# entireboard_v1.net
KiCad netlist of a schematic drawn in EAGLE
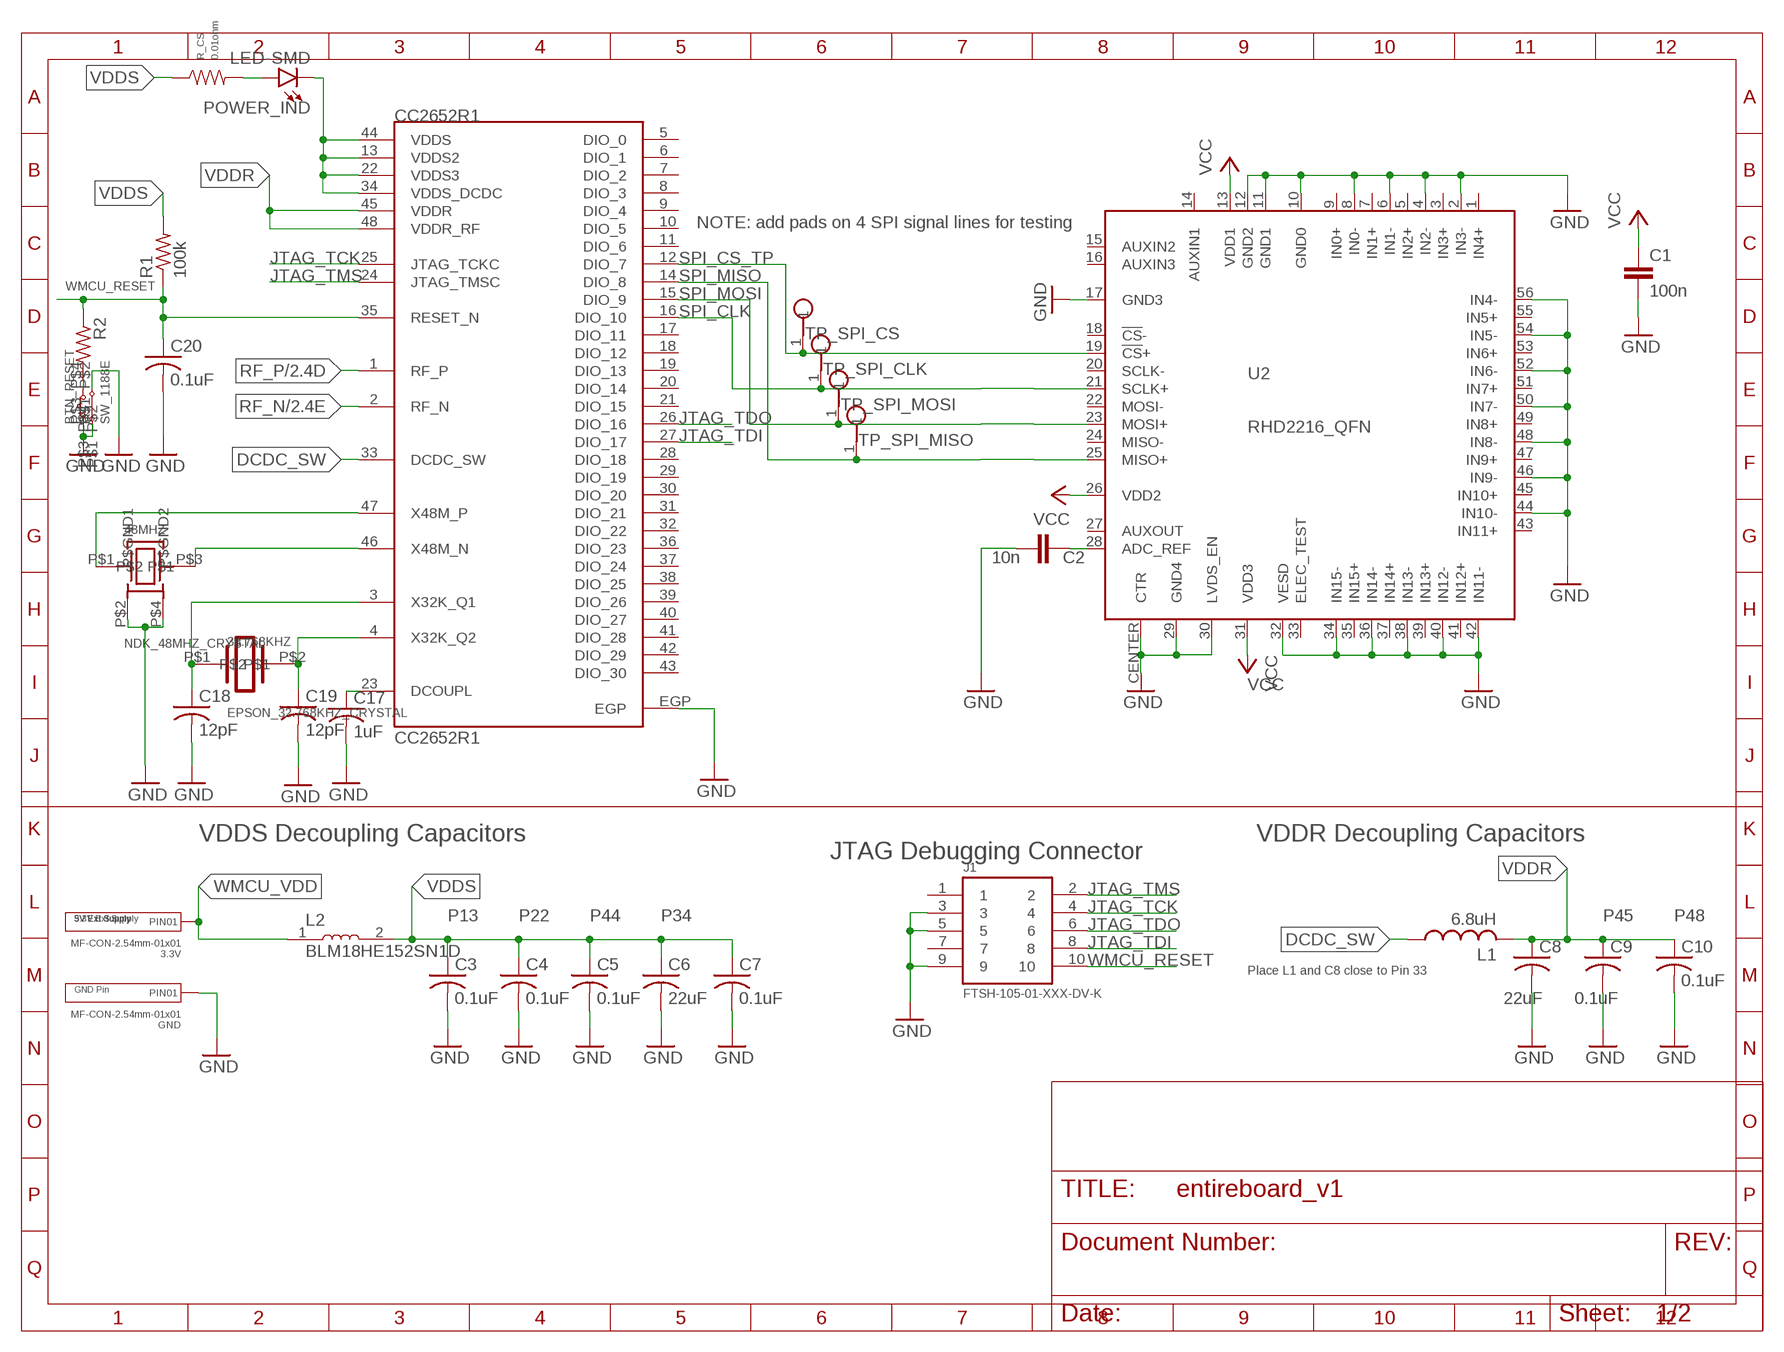
[diagram p0: schematic, sheet 1]
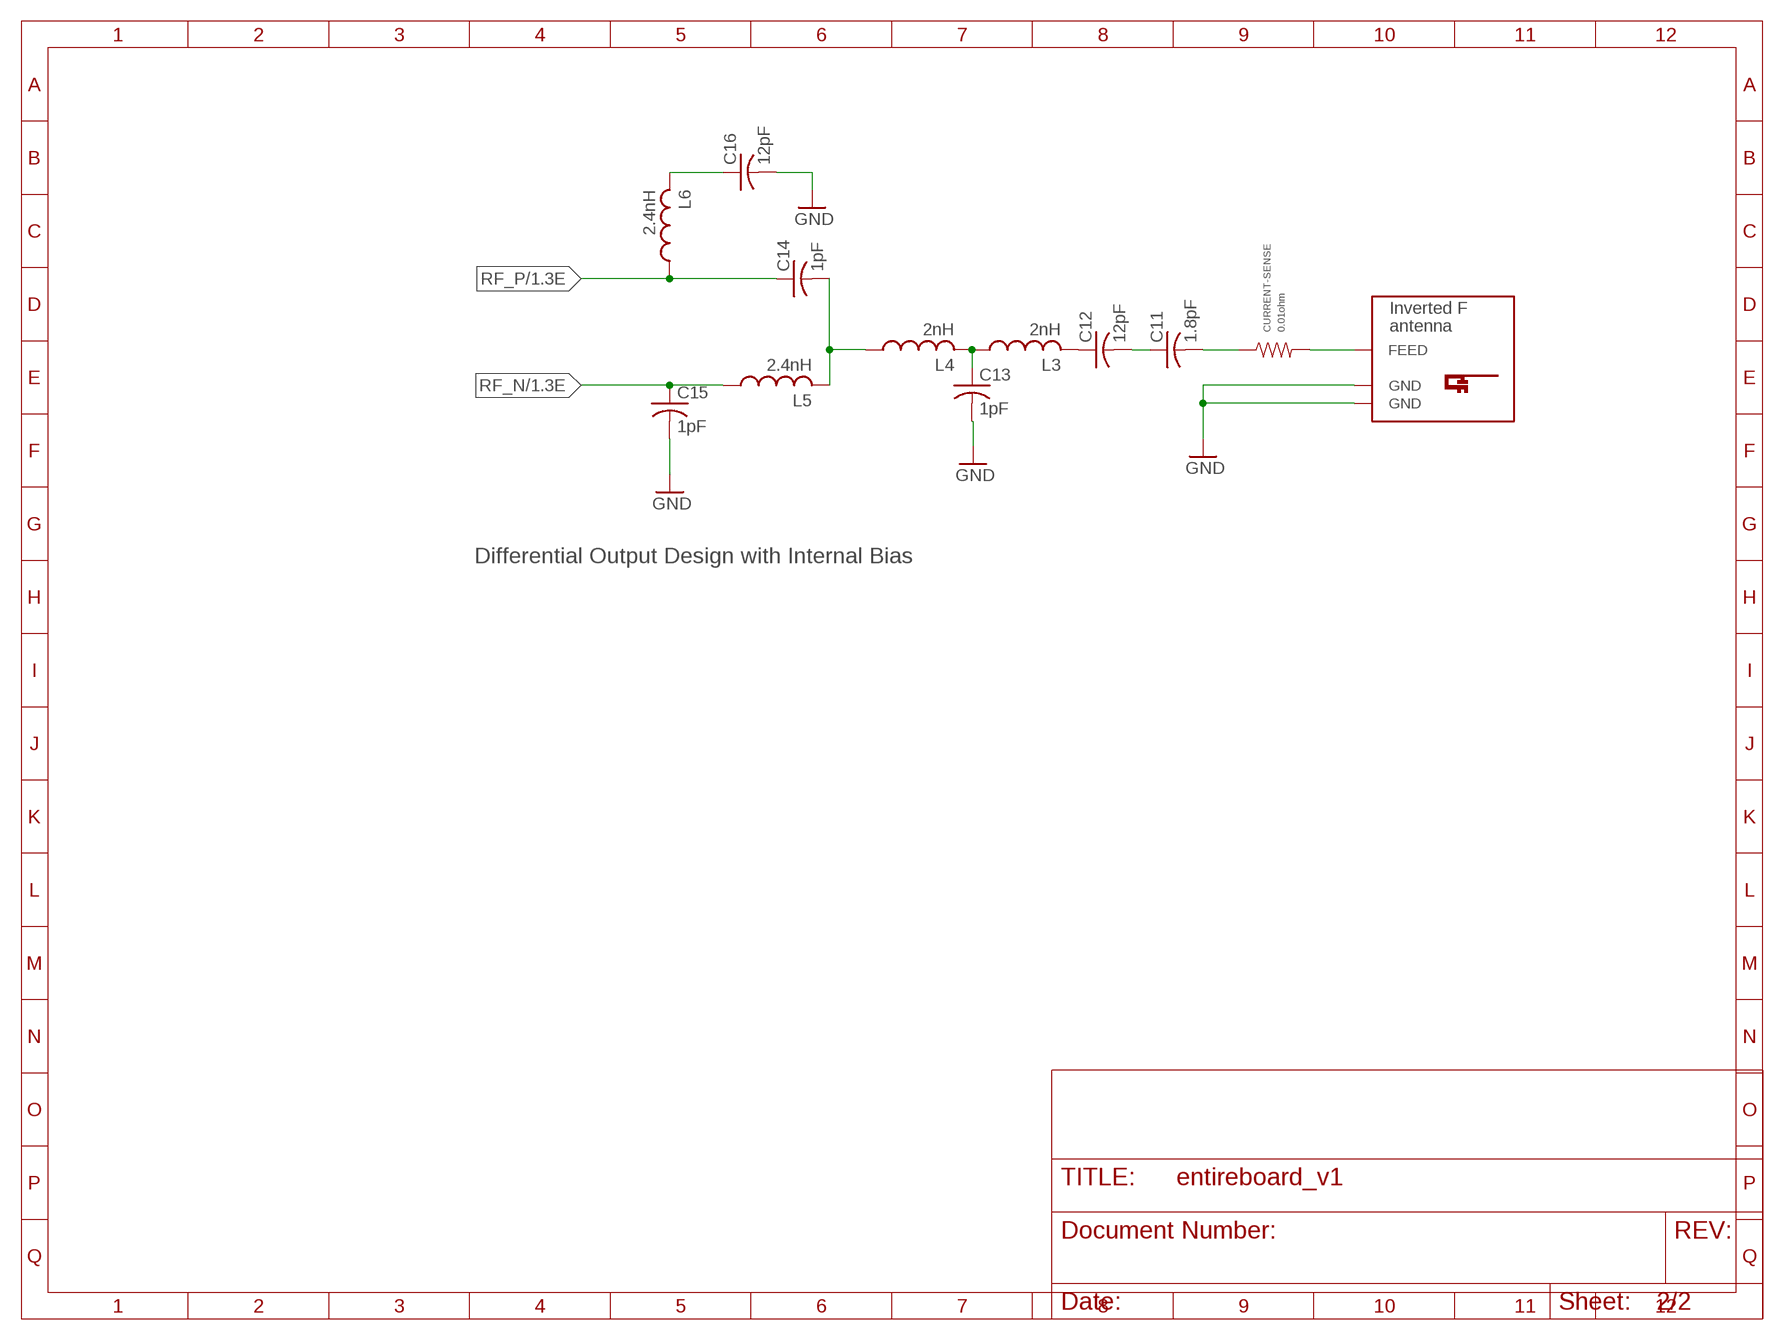
[diagram p1: schematic, sheet 2]

(export (version "E")
  (design (tool "Eeschema 10.0.6"))
  (components
    (comp (ref "3.3V")
      (value "MF-CON-2.54mm-01x01")
      (footprint "eagle-import:PTH_2.54MM_01X01")
      (fields (field (name "HOUSEPART") "YES"))
      (libsource (lib "eagle-import") (part "CON_01X01_PTH_2.54MM"))
    )
    (comp (ref "38.768KHZ")
      (value "EPSON_32.768KHZ_CRYSTAL")
      (footprint "eagle-import:2-SMD")
      (libsource (lib "eagle-import") (part "EPSON_32.768KHZ_CRYSTAL"))
    )
    (comp (ref "48MHZ")
      (value "NDK_48MHZ_CRYSTAL")
      (footprint "eagle-import:4-SMD")
      (libsource (lib "eagle-import") (part "NDK_48MHZ_CRYSTAL"))
    )
    (comp (ref "BTN_RESET")
      (value "SW_1188E")
      (footprint "eagle-import:SW_1188E")
      (libsource (lib "eagle-import") (part "SW_1188E"))
    )
    (comp (ref "C1")
      (value "100n")
      (footprint "eagle-import:0402")
      (libsource (lib "eagle-import") (part "C_0402"))
    )
    (comp (ref "C2")
      (value "10n")
      (footprint "eagle-import:0402")
      (libsource (lib "eagle-import") (part "C_0402"))
    )
    (comp (ref "C3")
      (value "0.1uF")
      (footprint "eagle-import:C0402")
      (libsource (lib "eagle-import") (part "C-USC0402"))
    )
    (comp (ref "C4")
      (value "0.1uF")
      (footprint "eagle-import:C0402")
      (libsource (lib "eagle-import") (part "C-USC0402"))
    )
    (comp (ref "C5")
      (value "0.1uF")
      (footprint "eagle-import:C0402")
      (libsource (lib "eagle-import") (part "C-USC0402"))
    )
    (comp (ref "C6")
      (value "22uF")
      (footprint "eagle-import:C0402")
      (libsource (lib "eagle-import") (part "C-USC0402"))
    )
    (comp (ref "C7")
      (value "0.1uF")
      (footprint "eagle-import:C0402")
      (libsource (lib "eagle-import") (part "C-USC0402"))
    )
    (comp (ref "C8")
      (value "22uF")
      (footprint "eagle-import:C0402")
      (libsource (lib "eagle-import") (part "C-USC0402"))
    )
    (comp (ref "C9")
      (value "0.1uF")
      (footprint "eagle-import:C0402")
      (libsource (lib "eagle-import") (part "C-USC0402"))
    )
    (comp (ref "C10")
      (value "0.1uF")
      (footprint "eagle-import:C0402")
      (libsource (lib "eagle-import") (part "C-USC0402"))
    )
    (comp (ref "C17")
      (value "1uF")
      (footprint "eagle-import:C0402")
      (libsource (lib "eagle-import") (part "C-USC0402"))
    )
    (comp (ref "C18")
      (value "12pF")
      (footprint "eagle-import:C0402")
      (libsource (lib "eagle-import") (part "C-USC0402"))
    )
    (comp (ref "C19")
      (value "12pF")
      (footprint "eagle-import:C0402")
      (libsource (lib "eagle-import") (part "C-USC0402"))
    )
    (comp (ref "C20")
      (value "0.1uF")
      (footprint "eagle-import:C0402")
      (libsource (lib "eagle-import") (part "C-USC0402"))
    )
    (comp (ref "CC2652R1")
      (value "CC2652R1")
      (footprint "eagle-import:CC2652R1_QFN-48")
      (libsource (lib "eagle-import") (part "CC2652R1"))
    )
    (comp (ref "GND")
      (value "MF-CON-2.54mm-01x01")
      (footprint "eagle-import:PTH_2.54MM_01X01")
      (fields (field (name "HOUSEPART") "YES"))
      (libsource (lib "eagle-import") (part "CON_01X01_PTH_2.54MM"))
    )
    (comp (ref "J1")
      (value "FTSH-105-01-XXX-DV-K")
      (footprint "eagle-import:FTSH-105-01-XXX-DV-K")
      (libsource (lib "eagle-import") (part "FTSH-105-01-XXX-DV-K"))
    )
    (comp (ref "L1")
      (value "6.8uH")
      (footprint "eagle-import:RHD2000_EVAL_BOARD_0805")
      (libsource (lib "eagle-import") (part "L-SMD"))
    )
    (comp (ref "L2")
      (value "BLM18HE152SN1D")
      (footprint "eagle-import:INDC1608X95")
      (fields (field (name "DIGI-KEY_PART_NUMBER") "490-5216-1-ND") (field (name "MF") "Murata Electronics"))
      (libsource (lib "eagle-import") (part "BLM18HE152SN1D"))
    )
    (comp (ref "POWER_IND")
      (value "LED-SMD")
      (footprint "eagle-import:RHD2000_EVAL_BOARD_0402")
      (libsource (lib "eagle-import") (part "LED-SMD"))
    )
    (comp (ref "R1")
      (value "100k")
      (footprint "eagle-import:R0402")
      (libsource (lib "eagle-import") (part "R-US_R0402"))
    )
    (comp (ref "R2")
      (value "R-US_R0402")
      (footprint "eagle-import:R0402")
      (libsource (lib "eagle-import") (part "R-US_R0402"))
    )
    (comp (ref "R_CS")
      (value "0.01ohm")
      (footprint "eagle-import:R0402")
      (libsource (lib "eagle-import") (part "RESISTOR_0402"))
    )
    (comp (ref "TP_SPI_CLK")
      (value "RHD2000_EVAL_BOARD_TESTPOINT_SMALL")
      (footprint "eagle-import:RHD2000_EVAL_BOARD_TESTPOINT_SMALL")
      (libsource (lib "eagle-import") (part "RHD2000_EVAL_BOARD_TESTPOINT_SMALL"))
    )
    (comp (ref "TP_SPI_CS")
      (value "RHD2000_EVAL_BOARD_TESTPOINT_SMALL")
      (footprint "eagle-import:RHD2000_EVAL_BOARD_TESTPOINT_SMALL")
      (libsource (lib "eagle-import") (part "RHD2000_EVAL_BOARD_TESTPOINT_SMALL"))
    )
    (comp (ref "TP_SPI_MISO")
      (value "RHD2000_EVAL_BOARD_TESTPOINT_SMALL")
      (footprint "eagle-import:RHD2000_EVAL_BOARD_TESTPOINT_SMALL")
      (libsource (lib "eagle-import") (part "RHD2000_EVAL_BOARD_TESTPOINT_SMALL"))
    )
    (comp (ref "TP_SPI_MOSI")
      (value "RHD2000_EVAL_BOARD_TESTPOINT_SMALL")
      (footprint "eagle-import:RHD2000_EVAL_BOARD_TESTPOINT_SMALL")
      (libsource (lib "eagle-import") (part "RHD2000_EVAL_BOARD_TESTPOINT_SMALL"))
    )
    (comp (ref "U2")
      (value "RHD2216_QFN")
      (footprint "eagle-import:QFN56_8_X_8_LARGE")
      (libsource (lib "eagle-import") (part "RHD2216_QFN"))
    )
    (comp (ref "C11")
      (value "1.8pF")
      (footprint "eagle-import:C0402")
      (libsource (lib "eagle-import") (part "C-USC0402"))
    )
    (comp (ref "C12")
      (value "12pF")
      (footprint "eagle-import:C0402")
      (libsource (lib "eagle-import") (part "C-USC0402"))
    )
    (comp (ref "C13")
      (value "1pF")
      (footprint "eagle-import:C0402")
      (libsource (lib "eagle-import") (part "C-USC0402"))
    )
    (comp (ref "C14")
      (value "1pF")
      (footprint "eagle-import:C0402")
      (libsource (lib "eagle-import") (part "C-USC0402"))
    )
    (comp (ref "C15")
      (value "1pF")
      (footprint "eagle-import:C0402")
      (libsource (lib "eagle-import") (part "C-USC0402"))
    )
    (comp (ref "C16")
      (value "12pF")
      (footprint "eagle-import:C0402")
      (libsource (lib "eagle-import") (part "C-USC0402"))
    )
    (comp (ref "CURRENT-SENSE")
      (value "0.01ohm")
      (footprint "eagle-import:R0402")
      (libsource (lib "eagle-import") (part "RESISTOR_0402"))
    )
    (comp (ref "L3")
      (value "2nH")
      (footprint "eagle-import:RHD2000_EVAL_BOARD_0805")
      (libsource (lib "eagle-import") (part "L-SMD"))
    )
    (comp (ref "L4")
      (value "2nH")
      (footprint "eagle-import:RHD2000_EVAL_BOARD_0805")
      (libsource (lib "eagle-import") (part "L-SMD"))
    )
    (comp (ref "L5")
      (value "2.4nH")
      (footprint "eagle-import:RHD2000_EVAL_BOARD_0805")
      (libsource (lib "eagle-import") (part "L-SMD"))
    )
    (comp (ref "L6")
      (value "2.4nH")
      (footprint "eagle-import:RHD2000_EVAL_BOARD_0805")
      (libsource (lib "eagle-import") (part "L-SMD"))
    )
    (comp (ref "U$2")
      (value "INVERTED_F_ANTENNA+0")
      (footprint "eagle-import:DN007+0")
      (libsource (lib "eagle-import") (part "INVERTED_F_ANTENNA+0"))
    )
  )
  (nets
    (net (code "1") (name "DCDC_SW") (class "Default")
      (node (ref "CC2652R1") (pin "33") (pinfunction "DCDC_SW_33") (pintype "bidirectional"))
      (node (ref "L1") (pin "1") (pinfunction "1_1") (pintype "passive"))
    )
    (net (code "2") (name "GND") (class "Default")
      (node (ref "48MHZ") (pin "P$2") (pinfunction "P$GND1_P$2") (pintype "bidirectional"))
      (node (ref "48MHZ") (pin "P$4") (pinfunction "P$GND2_P$4") (pintype "bidirectional"))
      (node (ref "BTN_RESET") (pin "P$1") (pinfunction "P$1_P$1") (pintype "bidirectional"))
      (node (ref "BTN_RESET") (pin "P$2") (pinfunction "P$2_P$2") (pintype "bidirectional"))
      (node (ref "BTN_RESET") (pin "P$3") (pinfunction "P$3_P$3") (pintype "bidirectional"))
      (node (ref "C1") (pin "2") (pinfunction "2_2") (pintype "passive"))
      (node (ref "C10") (pin "2") (pinfunction "2_2") (pintype "passive"))
      (node (ref "C13") (pin "2") (pinfunction "2_2") (pintype "passive"))
      (node (ref "C15") (pin "2") (pinfunction "2_2") (pintype "passive"))
      (node (ref "C16") (pin "2") (pinfunction "2_2") (pintype "passive"))
      (node (ref "C17") (pin "2") (pinfunction "2_2") (pintype "passive"))
      (node (ref "C18") (pin "2") (pinfunction "2_2") (pintype "passive"))
      (node (ref "C19") (pin "2") (pinfunction "2_2") (pintype "passive"))
      (node (ref "C2") (pin "2") (pinfunction "2_2") (pintype "passive"))
      (node (ref "C20") (pin "2") (pinfunction "2_2") (pintype "passive"))
      (node (ref "C3") (pin "2") (pinfunction "2_2") (pintype "passive"))
      (node (ref "C4") (pin "2") (pinfunction "2_2") (pintype "passive"))
      (node (ref "C5") (pin "2") (pinfunction "2_2") (pintype "passive"))
      (node (ref "C6") (pin "2") (pinfunction "2_2") (pintype "passive"))
      (node (ref "C7") (pin "2") (pinfunction "2_2") (pintype "passive"))
      (node (ref "C8") (pin "2") (pinfunction "2_2") (pintype "passive"))
      (node (ref "C9") (pin "2") (pinfunction "2_2") (pintype "passive"))
      (node (ref "CC2652R1") (pin "EGP") (pinfunction "EGP_EGP") (pintype "bidirectional"))
      (node (ref "GND") (pin "P$1") (pinfunction "PIN1_P$1") (pintype "bidirectional"))
      (node (ref "J1") (pin "3") (pinfunction "3_3") (pintype "bidirectional"))
      (node (ref "J1") (pin "5") (pinfunction "5_5") (pintype "bidirectional"))
      (node (ref "J1") (pin "9") (pinfunction "9_9") (pintype "bidirectional"))
      (node (ref "U$2") (pin "GND") (pinfunction "GND_GND") (pintype "bidirectional"))
      (node (ref "U$2") (pin "GND@1") (pinfunction "GND_GND@1") (pintype "bidirectional"))
      (node (ref "U2") (pin "10") (pinfunction "GND0_10") (pintype "input"))
      (node (ref "U2") (pin "11") (pinfunction "GND1_11") (pintype "power_in"))
      (node (ref "U2") (pin "12") (pinfunction "GND2_12") (pintype "power_in"))
      (node (ref "U2") (pin "17") (pinfunction "GND3_17") (pintype "power_in"))
      (node (ref "U2") (pin "2") (pinfunction "IN3-_2") (pintype "input"))
      (node (ref "U2") (pin "29") (pinfunction "GND4_29") (pintype "power_in"))
      (node (ref "U2") (pin "30") (pinfunction "LVDS_EN_30") (pintype "input"))
      (node (ref "U2") (pin "32") (pinfunction "VESD_32") (pintype "power_in"))
      (node (ref "U2") (pin "34") (pinfunction "IN15-_34") (pintype "input"))
      (node (ref "U2") (pin "36") (pinfunction "IN14-_36") (pintype "input"))
      (node (ref "U2") (pin "38") (pinfunction "IN13-_38") (pintype "input"))
      (node (ref "U2") (pin "4") (pinfunction "IN2-_4") (pintype "input"))
      (node (ref "U2") (pin "40") (pinfunction "IN12-_40") (pintype "input"))
      (node (ref "U2") (pin "42") (pinfunction "IN11-_42") (pintype "input"))
      (node (ref "U2") (pin "44") (pinfunction "IN10-_44") (pintype "input"))
      (node (ref "U2") (pin "46") (pinfunction "IN9-_46") (pintype "input"))
      (node (ref "U2") (pin "48") (pinfunction "IN8-_48") (pintype "input"))
      (node (ref "U2") (pin "50") (pinfunction "IN7-_50") (pintype "input"))
      (node (ref "U2") (pin "52") (pinfunction "IN6-_52") (pintype "input"))
      (node (ref "U2") (pin "54") (pinfunction "IN5-_54") (pintype "input"))
      (node (ref "U2") (pin "56") (pinfunction "IN4-_56") (pintype "input"))
      (node (ref "U2") (pin "6") (pinfunction "IN1-_6") (pintype "input"))
      (node (ref "U2") (pin "8") (pinfunction "IN0-_8") (pintype "input"))
      (node (ref "U2") (pin "CENTER") (pinfunction "CTR_CENTER") (pintype "power_in"))
    )
    (net (code "3") (name "JTAG_TCK") (class "Default")
      (node (ref "CC2652R1") (pin "25") (pinfunction "JTAG_TCKC_25") (pintype "bidirectional"))
      (node (ref "J1") (pin "4") (pinfunction "4_4") (pintype "bidirectional"))
    )
    (net (code "4") (name "JTAG_TDI") (class "Default")
      (node (ref "CC2652R1") (pin "27") (pinfunction "DIO_17_27") (pintype "bidirectional"))
      (node (ref "J1") (pin "8") (pinfunction "8_8") (pintype "bidirectional"))
    )
    (net (code "5") (name "JTAG_TDO") (class "Default")
      (node (ref "CC2652R1") (pin "26") (pinfunction "DIO_16_26") (pintype "bidirectional"))
      (node (ref "J1") (pin "6") (pinfunction "6_6") (pintype "bidirectional"))
    )
    (net (code "6") (name "JTAG_TMS") (class "Default")
      (node (ref "CC2652R1") (pin "24") (pinfunction "JTAG_TMSC_24") (pintype "bidirectional"))
      (node (ref "J1") (pin "2") (pinfunction "2_2") (pintype "bidirectional"))
    )
    (net (code "7") (name "Net-(48MHZ-P$2)") (class "Default")
      (node (ref "48MHZ") (pin "P$3") (pinfunction "P$2_P$3") (pintype "bidirectional"))
      (node (ref "CC2652R1") (pin "46") (pinfunction "X48M_N_46") (pintype "bidirectional"))
    )
    (net (code "8") (name "Net-(BTN_RESET-PadP$4)") (class "Default")
      (node (ref "BTN_RESET") (pin "P$4") (pinfunction "P$4_P$4") (pintype "bidirectional"))
      (node (ref "R2") (pin "2") (pinfunction "2_2") (pintype "passive"))
    )
    (net (code "9") (name "Net-(C11-Pad1)") (class "Default")
      (node (ref "C11") (pin "1") (pinfunction "1_1") (pintype "passive"))
      (node (ref "C12") (pin "2") (pinfunction "2_2") (pintype "passive"))
    )
    (net (code "10") (name "Net-(C11-Pad2)") (class "Default")
      (node (ref "C11") (pin "2") (pinfunction "2_2") (pintype "passive"))
      (node (ref "CURRENT-SENSE") (pin "P$1") (pinfunction "P$1_P$1") (pintype "passive"))
    )
    (net (code "11") (name "Net-(C12-Pad1)") (class "Default")
      (node (ref "C12") (pin "1") (pinfunction "1_1") (pintype "passive"))
      (node (ref "L3") (pin "2") (pinfunction "2_2") (pintype "passive"))
    )
    (net (code "12") (name "Net-(C13-Pad1)") (class "Default")
      (node (ref "C13") (pin "1") (pinfunction "1_1") (pintype "passive"))
      (node (ref "L3") (pin "1") (pinfunction "1_1") (pintype "passive"))
      (node (ref "L4") (pin "2") (pinfunction "2_2") (pintype "passive"))
    )
    (net (code "13") (name "Net-(C14-Pad2)") (class "Default")
      (node (ref "C14") (pin "2") (pinfunction "2_2") (pintype "passive"))
      (node (ref "L4") (pin "1") (pinfunction "1_1") (pintype "passive"))
      (node (ref "L5") (pin "2") (pinfunction "2_2") (pintype "passive"))
    )
    (net (code "14") (name "Net-(C16-Pad1)") (class "Default")
      (node (ref "C16") (pin "1") (pinfunction "1_1") (pintype "passive"))
      (node (ref "L6") (pin "2") (pinfunction "2_2") (pintype "passive"))
    )
    (net (code "15") (name "Net-(CC2652R1-DCOUPL)") (class "Default")
      (node (ref "C17") (pin "1") (pinfunction "1_1") (pintype "passive"))
      (node (ref "CC2652R1") (pin "23") (pinfunction "DCOUPL_23") (pintype "bidirectional"))
    )
    (net (code "16") (name "Net-(CC2652R1-X32K_Q1)") (class "Default")
      (node (ref "38.768KHZ") (pin "P$1") (pinfunction "P$1_P$1") (pintype "bidirectional"))
      (node (ref "C18") (pin "1") (pinfunction "1_1") (pintype "passive"))
      (node (ref "CC2652R1") (pin "3") (pinfunction "X32K_Q1_3") (pintype "bidirectional"))
    )
    (net (code "17") (name "Net-(CC2652R1-X32K_Q2)") (class "Default")
      (node (ref "38.768KHZ") (pin "P$2") (pinfunction "P$2_P$2") (pintype "bidirectional"))
      (node (ref "C19") (pin "1") (pinfunction "1_1") (pintype "passive"))
      (node (ref "CC2652R1") (pin "4") (pinfunction "X32K_Q2_4") (pintype "bidirectional"))
    )
    (net (code "18") (name "Net-(CC2652R1-X48M_P)") (class "Default")
      (node (ref "48MHZ") (pin "P$1") (pinfunction "P$1_P$1") (pintype "bidirectional"))
      (node (ref "CC2652R1") (pin "47") (pinfunction "X48M_P_47") (pintype "bidirectional"))
    )
    (net (code "19") (name "Net-(CURRENT-SENSE-PadP$2)") (class "Default")
      (node (ref "CURRENT-SENSE") (pin "P$2") (pinfunction "P$2_P$2") (pintype "passive"))
      (node (ref "U$2") (pin "FEED") (pinfunction "FEED_FEED") (pintype "bidirectional"))
    )
    (net (code "20") (name "Net-(POWER_IND-A)") (class "Default")
      (node (ref "POWER_IND") (pin "1") (pinfunction "A_1") (pintype "passive"))
      (node (ref "R_CS") (pin "P$2") (pinfunction "P$2_P$2") (pintype "passive"))
    )
    (net (code "21") (name "Net-(U2-ADC_REF)") (class "Default")
      (node (ref "C2") (pin "1") (pinfunction "1_1") (pintype "passive"))
      (node (ref "U2") (pin "28") (pinfunction "ADC_REF_28") (pintype "passive"))
    )
    (net (code "22") (name "RF_N") (class "Default")
      (node (ref "C15") (pin "1") (pinfunction "1_1") (pintype "passive"))
      (node (ref "CC2652R1") (pin "2") (pinfunction "RF_N_2") (pintype "bidirectional"))
      (node (ref "L5") (pin "1") (pinfunction "1_1") (pintype "passive"))
    )
    (net (code "23") (name "RF_P") (class "Default")
      (node (ref "C14") (pin "1") (pinfunction "1_1") (pintype "passive"))
      (node (ref "CC2652R1") (pin "1") (pinfunction "RF_P_1") (pintype "bidirectional"))
      (node (ref "L6") (pin "1") (pinfunction "1_1") (pintype "passive"))
    )
    (net (code "24") (name "SPI_CLK") (class "Default")
      (node (ref "CC2652R1") (pin "16") (pinfunction "DIO_10_16") (pintype "bidirectional"))
      (node (ref "TP_SPI_CLK") (pin "1") (pinfunction "1_1") (pintype "passive"))
      (node (ref "U2") (pin "21") (pinfunction "SCLK+_21") (pintype "input"))
    )
    (net (code "25") (name "SPI_CS_TP") (class "Default")
      (node (ref "CC2652R1") (pin "12") (pinfunction "DIO_7_12") (pintype "bidirectional"))
      (node (ref "TP_SPI_CS") (pin "1") (pinfunction "1_1") (pintype "passive"))
      (node (ref "U2") (pin "19") (pinfunction "~{CS}+_19") (pintype "input"))
    )
    (net (code "26") (name "SPI_MISO") (class "Default")
      (node (ref "CC2652R1") (pin "14") (pinfunction "DIO_8_14") (pintype "bidirectional"))
      (node (ref "TP_SPI_MISO") (pin "1") (pinfunction "1_1") (pintype "passive"))
      (node (ref "U2") (pin "25") (pinfunction "MISO+_25") (pintype "output"))
    )
    (net (code "27") (name "SPI_MOSI") (class "Default")
      (node (ref "CC2652R1") (pin "15") (pinfunction "DIO_9_15") (pintype "bidirectional"))
      (node (ref "TP_SPI_MOSI") (pin "1") (pinfunction "1_1") (pintype "passive"))
      (node (ref "U2") (pin "23") (pinfunction "MOSI+_23") (pintype "input"))
    )
    (net (code "28") (name "VCC") (class "Default")
      (node (ref "C1") (pin "1") (pinfunction "1_1") (pintype "passive"))
      (node (ref "U2") (pin "13") (pinfunction "VDD1_13") (pintype "power_in"))
      (node (ref "U2") (pin "26") (pinfunction "VDD2_26") (pintype "power_in"))
      (node (ref "U2") (pin "31") (pinfunction "VDD3_31") (pintype "power_in"))
    )
    (net (code "29") (name "VDDR") (class "Default")
      (node (ref "C10") (pin "1") (pinfunction "1_1") (pintype "passive"))
      (node (ref "C8") (pin "1") (pinfunction "1_1") (pintype "passive"))
      (node (ref "C9") (pin "1") (pinfunction "1_1") (pintype "passive"))
      (node (ref "CC2652R1") (pin "45") (pinfunction "VDDR_45") (pintype "bidirectional"))
      (node (ref "CC2652R1") (pin "48") (pinfunction "VDDR_RF_48") (pintype "bidirectional"))
      (node (ref "L1") (pin "2") (pinfunction "2_2") (pintype "passive"))
    )
    (net (code "30") (name "VDDS") (class "Default")
      (node (ref "C3") (pin "1") (pinfunction "1_1") (pintype "passive"))
      (node (ref "C4") (pin "1") (pinfunction "1_1") (pintype "passive"))
      (node (ref "C5") (pin "1") (pinfunction "1_1") (pintype "passive"))
      (node (ref "C6") (pin "1") (pinfunction "1_1") (pintype "passive"))
      (node (ref "C7") (pin "1") (pinfunction "1_1") (pintype "passive"))
      (node (ref "CC2652R1") (pin "13") (pinfunction "VDDS2_13") (pintype "bidirectional"))
      (node (ref "CC2652R1") (pin "22") (pinfunction "VDDS3_22") (pintype "bidirectional"))
      (node (ref "CC2652R1") (pin "34") (pinfunction "VDDS_DCDC_34") (pintype "bidirectional"))
      (node (ref "CC2652R1") (pin "44") (pinfunction "VDDS_44") (pintype "bidirectional"))
      (node (ref "L2") (pin "2") (pinfunction "2_2") (pintype "passive"))
      (node (ref "POWER_IND") (pin "2") (pinfunction "C_2") (pintype "passive"))
      (node (ref "R1") (pin "2") (pinfunction "2_2") (pintype "passive"))
      (node (ref "R_CS") (pin "P$1") (pinfunction "P$1_P$1") (pintype "passive"))
    )
    (net (code "31") (name "WMCU_RESET") (class "Default")
      (node (ref "C20") (pin "1") (pinfunction "1_1") (pintype "passive"))
      (node (ref "CC2652R1") (pin "35") (pinfunction "RESET_N_35") (pintype "bidirectional"))
      (node (ref "J1") (pin "10") (pinfunction "10_10") (pintype "bidirectional"))
      (node (ref "R1") (pin "1") (pinfunction "1_1") (pintype "passive"))
      (node (ref "R2") (pin "1") (pinfunction "1_1") (pintype "passive"))
    )
    (net (code "32") (name "WMCU_VDD") (class "Default")
      (node (ref "3.3V") (pin "P$1") (pinfunction "PIN1_P$1") (pintype "bidirectional"))
      (node (ref "L2") (pin "1") (pinfunction "1_1") (pintype "passive"))
    )
    (net (code "33") (name "unconnected-(CC2652R1-DIO_0-Pad5)") (class "Default")
      (node (ref "CC2652R1") (pin "5") (pinfunction "DIO_0_5") (pintype "bidirectional"))
    )
    (net (code "34") (name "unconnected-(CC2652R1-DIO_1-Pad6)") (class "Default")
      (node (ref "CC2652R1") (pin "6") (pinfunction "DIO_1_6") (pintype "bidirectional"))
    )
    (net (code "35") (name "unconnected-(CC2652R1-DIO_2-Pad7)") (class "Default")
      (node (ref "CC2652R1") (pin "7") (pinfunction "DIO_2_7") (pintype "bidirectional"))
    )
    (net (code "36") (name "unconnected-(CC2652R1-DIO_3-Pad8)") (class "Default")
      (node (ref "CC2652R1") (pin "8") (pinfunction "DIO_3_8") (pintype "bidirectional"))
    )
    (net (code "37") (name "unconnected-(CC2652R1-DIO_4-Pad9)") (class "Default")
      (node (ref "CC2652R1") (pin "9") (pinfunction "DIO_4_9") (pintype "bidirectional"))
    )
    (net (code "38") (name "unconnected-(CC2652R1-DIO_5-Pad10)") (class "Default")
      (node (ref "CC2652R1") (pin "10") (pinfunction "DIO_5_10") (pintype "bidirectional"))
    )
    (net (code "39") (name "unconnected-(CC2652R1-DIO_6-Pad11)") (class "Default")
      (node (ref "CC2652R1") (pin "11") (pinfunction "DIO_6_11") (pintype "bidirectional"))
    )
    (net (code "40") (name "unconnected-(CC2652R1-DIO_11-Pad17)") (class "Default")
      (node (ref "CC2652R1") (pin "17") (pinfunction "DIO_11_17") (pintype "bidirectional"))
    )
    (net (code "41") (name "unconnected-(CC2652R1-DIO_12-Pad18)") (class "Default")
      (node (ref "CC2652R1") (pin "18") (pinfunction "DIO_12_18") (pintype "bidirectional"))
    )
    (net (code "42") (name "unconnected-(CC2652R1-DIO_13-Pad19)") (class "Default")
      (node (ref "CC2652R1") (pin "19") (pinfunction "DIO_13_19") (pintype "bidirectional"))
    )
    (net (code "43") (name "unconnected-(CC2652R1-DIO_14-Pad20)") (class "Default")
      (node (ref "CC2652R1") (pin "20") (pinfunction "DIO_14_20") (pintype "bidirectional"))
    )
    (net (code "44") (name "unconnected-(CC2652R1-DIO_15-Pad21)") (class "Default")
      (node (ref "CC2652R1") (pin "21") (pinfunction "DIO_15_21") (pintype "bidirectional"))
    )
    (net (code "45") (name "unconnected-(CC2652R1-DIO_18-Pad28)") (class "Default")
      (node (ref "CC2652R1") (pin "28") (pinfunction "DIO_18_28") (pintype "bidirectional"))
    )
    (net (code "46") (name "unconnected-(CC2652R1-DIO_19-Pad29)") (class "Default")
      (node (ref "CC2652R1") (pin "29") (pinfunction "DIO_19_29") (pintype "bidirectional"))
    )
    (net (code "47") (name "unconnected-(CC2652R1-DIO_20-Pad30)") (class "Default")
      (node (ref "CC2652R1") (pin "30") (pinfunction "DIO_20_30") (pintype "bidirectional"))
    )
    (net (code "48") (name "unconnected-(CC2652R1-DIO_21-Pad31)") (class "Default")
      (node (ref "CC2652R1") (pin "31") (pinfunction "DIO_21_31") (pintype "bidirectional"))
    )
    (net (code "49") (name "unconnected-(CC2652R1-DIO_22-Pad32)") (class "Default")
      (node (ref "CC2652R1") (pin "32") (pinfunction "DIO_22_32") (pintype "bidirectional"))
    )
    (net (code "50") (name "unconnected-(CC2652R1-DIO_23-Pad36)") (class "Default")
      (node (ref "CC2652R1") (pin "36") (pinfunction "DIO_23_36") (pintype "bidirectional"))
    )
    (net (code "51") (name "unconnected-(CC2652R1-DIO_24-Pad37)") (class "Default")
      (node (ref "CC2652R1") (pin "37") (pinfunction "DIO_24_37") (pintype "bidirectional"))
    )
    (net (code "52") (name "unconnected-(CC2652R1-DIO_25-Pad38)") (class "Default")
      (node (ref "CC2652R1") (pin "38") (pinfunction "DIO_25_38") (pintype "bidirectional"))
    )
    (net (code "53") (name "unconnected-(CC2652R1-DIO_26-Pad39)") (class "Default")
      (node (ref "CC2652R1") (pin "39") (pinfunction "DIO_26_39") (pintype "bidirectional"))
    )
    (net (code "54") (name "unconnected-(CC2652R1-DIO_27-Pad40)") (class "Default")
      (node (ref "CC2652R1") (pin "40") (pinfunction "DIO_27_40") (pintype "bidirectional"))
    )
    (net (code "55") (name "unconnected-(CC2652R1-DIO_28-Pad41)") (class "Default")
      (node (ref "CC2652R1") (pin "41") (pinfunction "DIO_28_41") (pintype "bidirectional"))
    )
    (net (code "56") (name "unconnected-(CC2652R1-DIO_29-Pad42)") (class "Default")
      (node (ref "CC2652R1") (pin "42") (pinfunction "DIO_29_42") (pintype "bidirectional"))
    )
    (net (code "57") (name "unconnected-(CC2652R1-DIO_30-Pad43)") (class "Default")
      (node (ref "CC2652R1") (pin "43") (pinfunction "DIO_30_43") (pintype "bidirectional"))
    )
    (net (code "58") (name "unconnected-(J1-Pad1)") (class "Default")
      (node (ref "J1") (pin "1") (pinfunction "1_1") (pintype "bidirectional"))
    )
    (net (code "59") (name "unconnected-(J1-Pad7)") (class "Default")
      (node (ref "J1") (pin "7") (pinfunction "7_7") (pintype "bidirectional"))
    )
    (net (code "60") (name "unconnected-(U2-AUXIN1-Pad14)") (class "Default")
      (node (ref "U2") (pin "14") (pinfunction "AUXIN1_14") (pintype "input"))
    )
    (net (code "61") (name "unconnected-(U2-AUXIN2-Pad15)") (class "Default")
      (node (ref "U2") (pin "15") (pinfunction "AUXIN2_15") (pintype "input"))
    )
    (net (code "62") (name "unconnected-(U2-AUXIN3-Pad16)") (class "Default")
      (node (ref "U2") (pin "16") (pinfunction "AUXIN3_16") (pintype "input"))
    )
    (net (code "63") (name "unconnected-(U2-AUXOUT-Pad27)") (class "Default")
      (node (ref "U2") (pin "27") (pinfunction "AUXOUT_27") (pintype "tri_state"))
    )
    (net (code "64") (name "unconnected-(U2-ELEC_TEST-Pad33)") (class "Default")
      (node (ref "U2") (pin "33") (pinfunction "ELEC_TEST_33") (pintype "input"))
    )
    (net (code "65") (name "unconnected-(U2-IN0+-Pad9)") (class "Default")
      (node (ref "U2") (pin "9") (pinfunction "IN0+_9") (pintype "input"))
    )
    (net (code "66") (name "unconnected-(U2-IN1+-Pad7)") (class "Default")
      (node (ref "U2") (pin "7") (pinfunction "IN1+_7") (pintype "input"))
    )
    (net (code "67") (name "unconnected-(U2-IN2+-Pad5)") (class "Default")
      (node (ref "U2") (pin "5") (pinfunction "IN2+_5") (pintype "input"))
    )
    (net (code "68") (name "unconnected-(U2-IN3+-Pad3)") (class "Default")
      (node (ref "U2") (pin "3") (pinfunction "IN3+_3") (pintype "input"))
    )
    (net (code "69") (name "unconnected-(U2-IN4+-Pad1)") (class "Default")
      (node (ref "U2") (pin "1") (pinfunction "IN4+_1") (pintype "input"))
    )
    (net (code "70") (name "unconnected-(U2-IN5+-Pad55)") (class "Default")
      (node (ref "U2") (pin "55") (pinfunction "IN5+_55") (pintype "input"))
    )
    (net (code "71") (name "unconnected-(U2-IN6+-Pad53)") (class "Default")
      (node (ref "U2") (pin "53") (pinfunction "IN6+_53") (pintype "input"))
    )
    (net (code "72") (name "unconnected-(U2-IN7+-Pad51)") (class "Default")
      (node (ref "U2") (pin "51") (pinfunction "IN7+_51") (pintype "input"))
    )
    (net (code "73") (name "unconnected-(U2-IN8+-Pad49)") (class "Default")
      (node (ref "U2") (pin "49") (pinfunction "IN8+_49") (pintype "input"))
    )
    (net (code "74") (name "unconnected-(U2-IN9+-Pad47)") (class "Default")
      (node (ref "U2") (pin "47") (pinfunction "IN9+_47") (pintype "input"))
    )
    (net (code "75") (name "unconnected-(U2-IN10+-Pad45)") (class "Default")
      (node (ref "U2") (pin "45") (pinfunction "IN10+_45") (pintype "input"))
    )
    (net (code "76") (name "unconnected-(U2-IN11+-Pad43)") (class "Default")
      (node (ref "U2") (pin "43") (pinfunction "IN11+_43") (pintype "input"))
    )
    (net (code "77") (name "unconnected-(U2-IN12+-Pad41)") (class "Default")
      (node (ref "U2") (pin "41") (pinfunction "IN12+_41") (pintype "input"))
    )
    (net (code "78") (name "unconnected-(U2-IN13+-Pad39)") (class "Default")
      (node (ref "U2") (pin "39") (pinfunction "IN13+_39") (pintype "input"))
    )
    (net (code "79") (name "unconnected-(U2-IN14+-Pad37)") (class "Default")
      (node (ref "U2") (pin "37") (pinfunction "IN14+_37") (pintype "input"))
    )
    (net (code "80") (name "unconnected-(U2-IN15+-Pad35)") (class "Default")
      (node (ref "U2") (pin "35") (pinfunction "IN15+_35") (pintype "input"))
    )
    (net (code "81") (name "unconnected-(U2-MISO--Pad24)") (class "Default")
      (node (ref "U2") (pin "24") (pinfunction "MISO-_24") (pintype "output"))
    )
    (net (code "82") (name "unconnected-(U2-MOSI--Pad22)") (class "Default")
      (node (ref "U2") (pin "22") (pinfunction "MOSI-_22") (pintype "input"))
    )
    (net (code "83") (name "unconnected-(U2-SCLK--Pad20)") (class "Default")
      (node (ref "U2") (pin "20") (pinfunction "SCLK-_20") (pintype "input"))
    )
    (net (code "84") (name "unconnected-(U2-~{CS}--Pad18)") (class "Default")
      (node (ref "U2") (pin "18") (pinfunction "~{CS}-_18") (pintype "input"))
    )
  )
)
